# Multitouch_alaMTK.net
KiCad netlist of a schematic drawn in EasyEDA
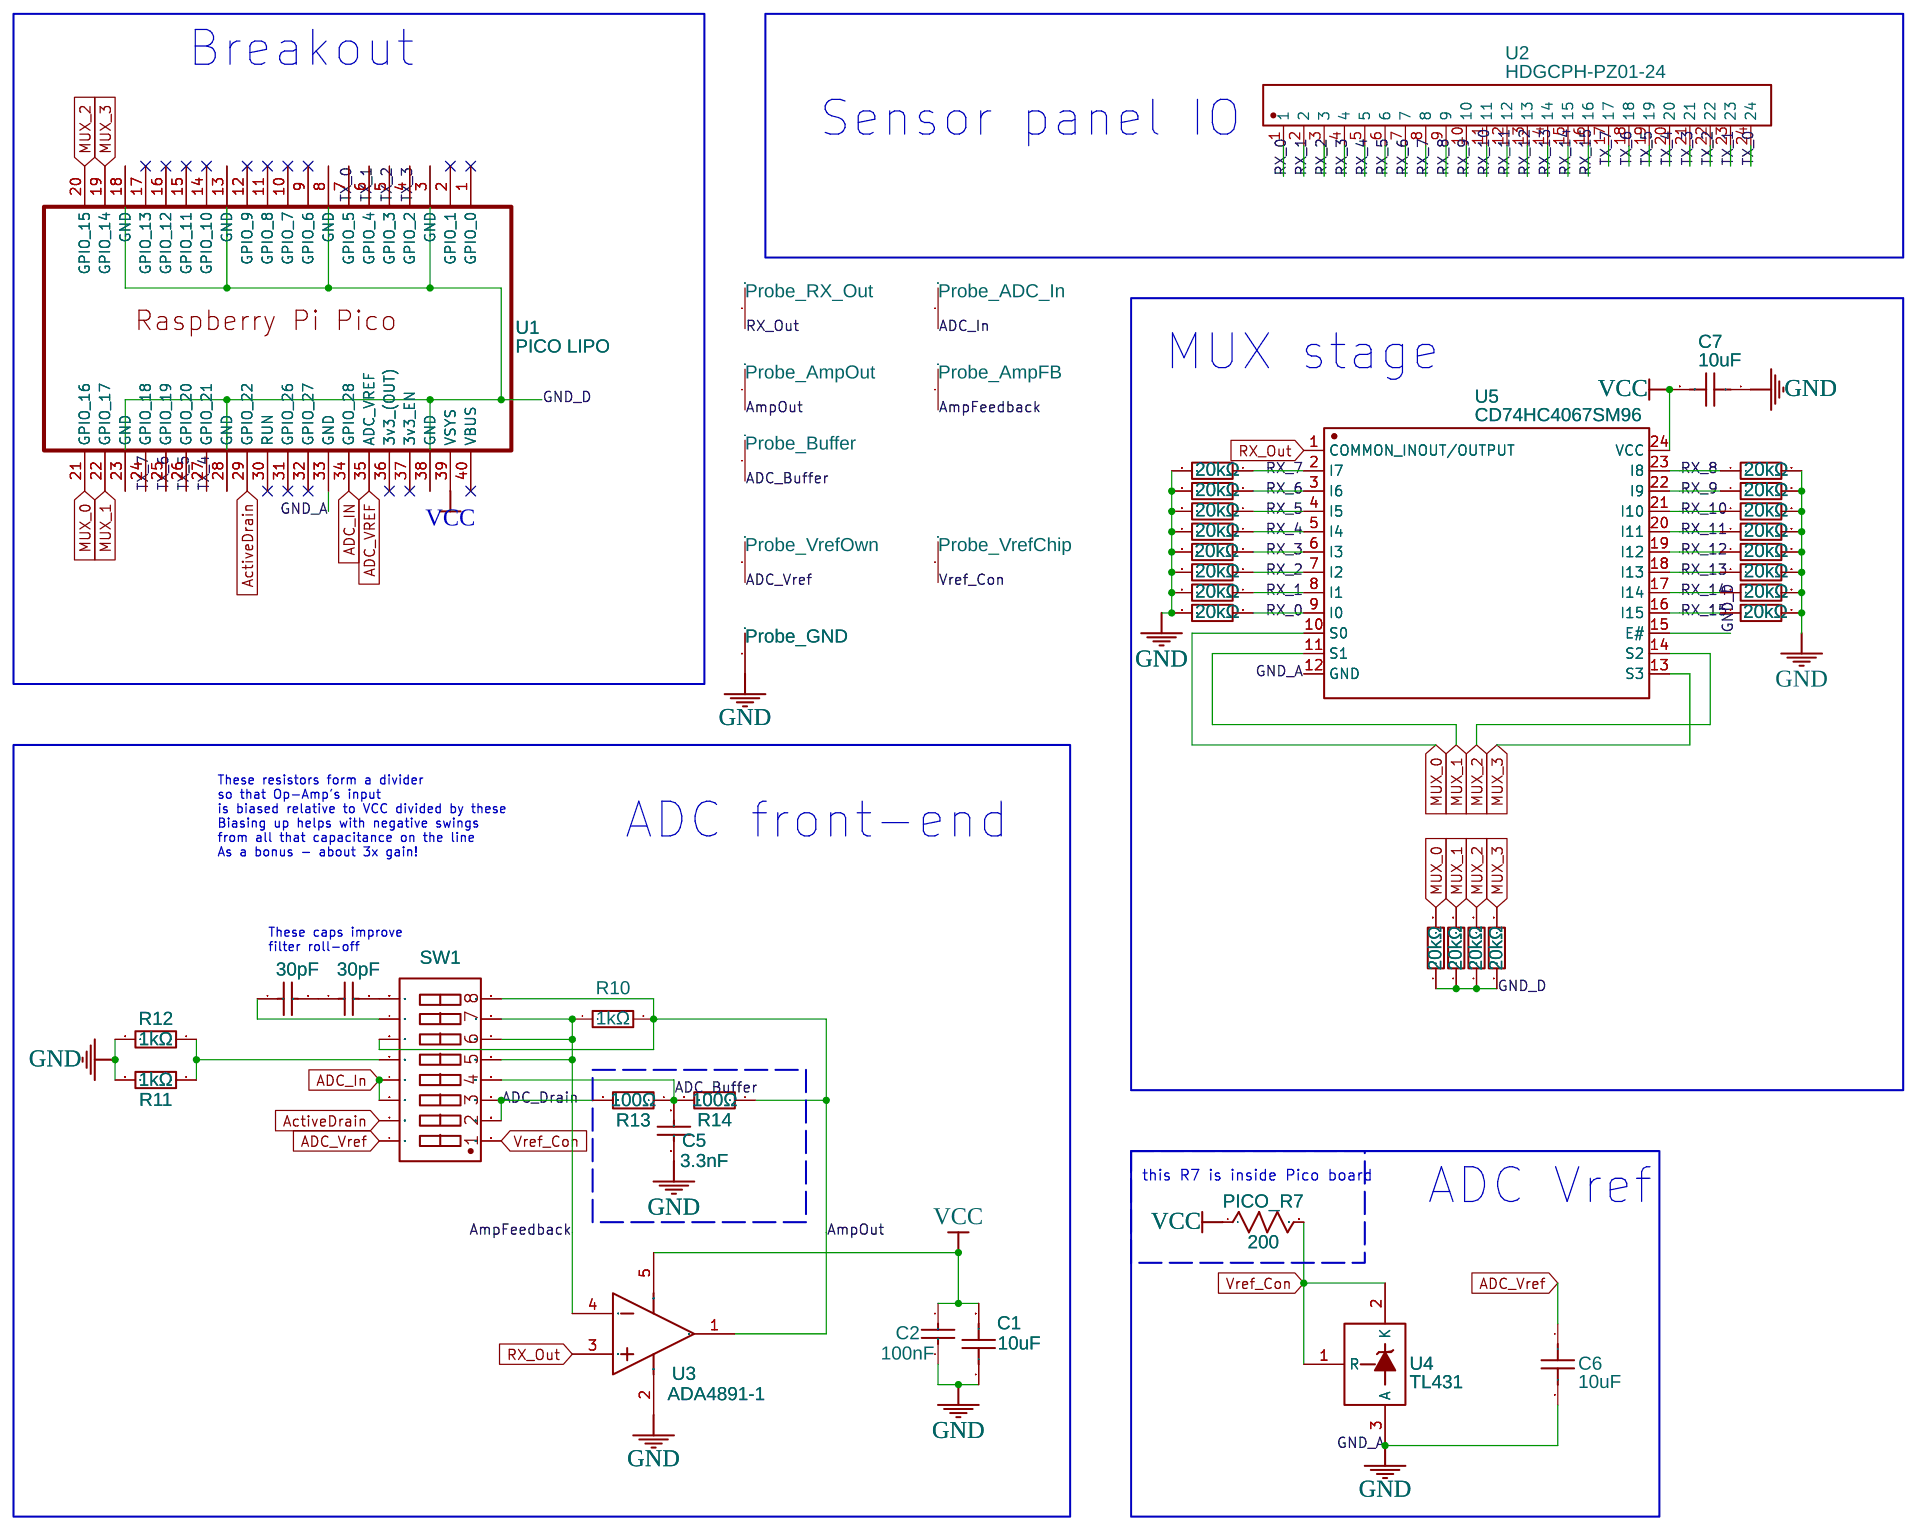
[diagram p0: schematic sheet]

(export (version "E")
  (design (tool "Eeschema 10.0.6"))
  (components
    (comp (ref "ADCB") (value "Probe_Buffer") (libsource (lib "") (part "SINGLE_PIN_1")))
    (comp (ref "ADCI") (value "Probe_ADC_In") (libsource (lib "") (part "SINGLE_PIN_7")))
    (comp (ref "ADCV") (value "Probe_VrefOwn") (libsource (lib "") (part "SINGLE_PIN_2")))
    (comp (ref "AFB") (value "Probe_AmpFB") (libsource (lib "") (part "SINGLE_PIN_3")))
    (comp (ref "AO") (value "Probe_AmpOut") (libsource (lib "") (part "SINGLE_PIN_5")))
    (comp (ref "C1")
      (value "10uF")
      (fields
        (field (name "Manufacturer Part") "CL10A106KP8NNNC")
        (field (name "Manufacturer") "SAMSUNG(三星)")
      )
      (libsource (lib "") (part "CL10A106KP8NNNC"))
    )
    (comp (ref "C2")
      (value "100nF")
      (fields
        (field (name "Manufacturer Part") "CL05B104KO5NNNC")
        (field (name "Manufacturer") "SAMSUNG(三星)")
      )
      (libsource (lib "") (part "CL05B104KO5NNNC"))
    )
    (comp (ref "C3")
      (value "30pF")
      (fields (field (name "Manufacturer Part") "0603CG300J500NT") (field (name "Manufacturer") "FH(风华)"))
      (libsource (lib "") (part "0603CG300J500NT"))
    )
    (comp (ref "C4")
      (value "30pF")
      (fields (field (name "Manufacturer Part") "0603CG300J500NT") (field (name "Manufacturer") "FH(风华)"))
      (libsource (lib "") (part "0603CG300J500NT"))
    )
    (comp (ref "C5")
      (value "3.3nF")
      (fields
        (field (name "Manufacturer Part") "CL10B332KB8NNNC")
        (field (name "Manufacturer") "SAMSUNG(三星)")
      )
      (libsource (lib "") (part "CL10B332KB8NNNC"))
    )
    (comp (ref "C6")
      (value "10uF")
      (fields
        (field (name "Manufacturer Part") "CL10A106KP8NNNC")
        (field (name "Manufacturer") "SAMSUNG(三星)")
      )
      (libsource (lib "") (part "CL10A106KP8NNNC_2"))
    )
    (comp (ref "C7")
      (value "10uF")
      (fields
        (field (name "Manufacturer Part") "CL10A106KP8NNNC")
        (field (name "Manufacturer") "SAMSUNG(三星)")
      )
      (libsource (lib "") (part "CL10A106KP8NNNC_1"))
    )
    (comp (ref "J2") (value "Probe_GND") (libsource (lib "") (part "SINGLE_PIN_4")))
    (comp (ref "PICO_R7") (value "200") (libsource (lib "") (part "R_0603_US")))
    (comp (ref "R10")
      (value "1kΩ")
      (fields
        (field (name "Manufacturer Part") "0402WGF1001TCE")
        (field (name "Manufacturer") "UNI-ROYAL(厚声)")
      )
      (libsource (lib "") (part "0402WGF1001TCE"))
    )
    (comp (ref "R11")
      (value "1kΩ")
      (fields
        (field (name "Manufacturer Part") "0402WGF1001TCE")
        (field (name "Manufacturer") "UNI-ROYAL(厚声)")
      )
      (libsource (lib "") (part "0402WGF1001TCE_1"))
    )
    (comp (ref "R12")
      (value "1kΩ")
      (fields
        (field (name "Manufacturer Part") "0402WGF1001TCE")
        (field (name "Manufacturer") "UNI-ROYAL(厚声)")
      )
      (libsource (lib "") (part "0402WGF1001TCE_1"))
    )
    (comp (ref "R13")
      (value "100Ω")
      (fields
        (field (name "Manufacturer Part") "0402WGF1000TCE")
        (field (name "Manufacturer") "UNI-ROYAL(厚声)")
      )
      (libsource (lib "") (part "0402WGF1000TCE"))
    )
    (comp (ref "R14")
      (value "100Ω")
      (fields
        (field (name "Manufacturer Part") "0402WGF1000TCE")
        (field (name "Manufacturer") "UNI-ROYAL(厚声)")
      )
      (libsource (lib "") (part "0402WGF1000TCE"))
    )
    (comp (ref "R15")
      (value "20kΩ")
      (fields
        (field (name "Manufacturer Part") "0402WGF2002TCE")
        (field (name "Manufacturer") "UNI-ROYAL(厚声)")
      )
      (libsource (lib "") (part "0402WGF2002TCE_1"))
    )
    (comp (ref "R16")
      (value "20kΩ")
      (fields
        (field (name "Manufacturer Part") "0402WGF2002TCE")
        (field (name "Manufacturer") "UNI-ROYAL(厚声)")
      )
      (libsource (lib "") (part "0402WGF2002TCE_1"))
    )
    (comp (ref "R17")
      (value "20kΩ")
      (fields
        (field (name "Manufacturer Part") "0402WGF2002TCE")
        (field (name "Manufacturer") "UNI-ROYAL(厚声)")
      )
      (libsource (lib "") (part "0402WGF2002TCE_1"))
    )
    (comp (ref "R18")
      (value "20kΩ")
      (fields
        (field (name "Manufacturer Part") "0402WGF2002TCE")
        (field (name "Manufacturer") "UNI-ROYAL(厚声)")
      )
      (libsource (lib "") (part "0402WGF2002TCE_1"))
    )
    (comp (ref "R19")
      (value "20kΩ")
      (fields
        (field (name "Manufacturer Part") "0402WGF2002TCE")
        (field (name "Manufacturer") "UNI-ROYAL(厚声)")
      )
      (libsource (lib "") (part "0402WGF2002TCE"))
    )
    (comp (ref "R20")
      (value "20kΩ")
      (fields
        (field (name "Manufacturer Part") "0402WGF2002TCE")
        (field (name "Manufacturer") "UNI-ROYAL(厚声)")
      )
      (libsource (lib "") (part "0402WGF2002TCE_2"))
    )
    (comp (ref "R21")
      (value "20kΩ")
      (fields
        (field (name "Manufacturer Part") "0402WGF2002TCE")
        (field (name "Manufacturer") "UNI-ROYAL(厚声)")
      )
      (libsource (lib "") (part "0402WGF2002TCE_2"))
    )
    (comp (ref "R22")
      (value "20kΩ")
      (fields
        (field (name "Manufacturer Part") "0402WGF2002TCE")
        (field (name "Manufacturer") "UNI-ROYAL(厚声)")
      )
      (libsource (lib "") (part "0402WGF2002TCE_2"))
    )
    (comp (ref "R23")
      (value "20kΩ")
      (fields
        (field (name "Manufacturer Part") "0402WGF2002TCE")
        (field (name "Manufacturer") "UNI-ROYAL(厚声)")
      )
      (libsource (lib "") (part "0402WGF2002TCE_2"))
    )
    (comp (ref "R24")
      (value "20kΩ")
      (fields
        (field (name "Manufacturer Part") "0402WGF2002TCE")
        (field (name "Manufacturer") "UNI-ROYAL(厚声)")
      )
      (libsource (lib "") (part "0402WGF2002TCE_2"))
    )
    (comp (ref "R25")
      (value "20kΩ")
      (fields
        (field (name "Manufacturer Part") "0402WGF2002TCE")
        (field (name "Manufacturer") "UNI-ROYAL(厚声)")
      )
      (libsource (lib "") (part "0402WGF2002TCE_2"))
    )
    (comp (ref "R26")
      (value "20kΩ")
      (fields
        (field (name "Manufacturer Part") "0402WGF2002TCE")
        (field (name "Manufacturer") "UNI-ROYAL(厚声)")
      )
      (libsource (lib "") (part "0402WGF2002TCE_2"))
    )
    (comp (ref "R27")
      (value "20kΩ")
      (fields
        (field (name "Manufacturer Part") "0402WGF2002TCE")
        (field (name "Manufacturer") "UNI-ROYAL(厚声)")
      )
      (libsource (lib "") (part "0402WGF2002TCE_2"))
    )
    (comp (ref "R28")
      (value "20kΩ")
      (fields
        (field (name "Manufacturer Part") "0402WGF2002TCE")
        (field (name "Manufacturer") "UNI-ROYAL(厚声)")
      )
      (libsource (lib "") (part "0402WGF2002TCE"))
    )
    (comp (ref "R29")
      (value "20kΩ")
      (fields
        (field (name "Manufacturer Part") "0402WGF2002TCE")
        (field (name "Manufacturer") "UNI-ROYAL(厚声)")
      )
      (libsource (lib "") (part "0402WGF2002TCE"))
    )
    (comp (ref "R30")
      (value "20kΩ")
      (fields
        (field (name "Manufacturer Part") "0402WGF2002TCE")
        (field (name "Manufacturer") "UNI-ROYAL(厚声)")
      )
      (libsource (lib "") (part "0402WGF2002TCE"))
    )
    (comp (ref "R31")
      (value "20kΩ")
      (fields
        (field (name "Manufacturer Part") "0402WGF2002TCE")
        (field (name "Manufacturer") "UNI-ROYAL(厚声)")
      )
      (libsource (lib "") (part "0402WGF2002TCE"))
    )
    (comp (ref "R32")
      (value "20kΩ")
      (fields
        (field (name "Manufacturer Part") "0402WGF2002TCE")
        (field (name "Manufacturer") "UNI-ROYAL(厚声)")
      )
      (libsource (lib "") (part "0402WGF2002TCE"))
    )
    (comp (ref "R33")
      (value "20kΩ")
      (fields
        (field (name "Manufacturer Part") "0402WGF2002TCE")
        (field (name "Manufacturer") "UNI-ROYAL(厚声)")
      )
      (libsource (lib "") (part "0402WGF2002TCE"))
    )
    (comp (ref "R34")
      (value "20kΩ")
      (fields
        (field (name "Manufacturer Part") "0402WGF2002TCE")
        (field (name "Manufacturer") "UNI-ROYAL(厚声)")
      )
      (libsource (lib "") (part "0402WGF2002TCE"))
    )
    (comp (ref "RXO") (value "Probe_RX_Out") (libsource (lib "") (part "SINGLE_PIN")))
    (comp (ref "SW1")
      (value "KF1027B-08P-L00-DFT-01B")
      (fields (field (name "Manufacturer") "凯峰"))
      (libsource (lib "") (part "KF1027B-08P-L00-DFT-01B"))
    )
    (comp (ref "U1") (value "PICO LIPO") (libsource (lib "") (part "RASPBERRY PI PICO WITH 3D MODEL COPY")))
    (comp (ref "U2")
      (value "HDGCPH-PZ01-24")
      (fields (field (name "Manufacturer") "HDGC(华德共创)"))
      (libsource (lib "") (part "HDGCPH-PZ01-24"))
    )
    (comp (ref "U3")
      (value "ADA4891-1")
      (fields (field (name "Manufacturer Part") "ADA4891-1ARJZ-R7") (field (name "Manufacturer") "ADI(亚德诺)"))
      (libsource (lib "") (part "ADA4891-1ARJZ-R7"))
    )
    (comp (ref "U4")
      (value "TL431")
      (fields (field (name "Manufacturer Part") "CJ431") (field (name "Manufacturer") "CJ(江苏长电/长晶)"))
      (libsource (lib "") (part "CJ431_C3113"))
    )
    (comp (ref "U5")
      (value "CD74HC4067SM96")
      (fields (field (name "Manufacturer") "TI(德州仪器)"))
      (libsource (lib "") (part "CD74HC4067SM96"))
    )
    (comp (ref "VREF") (value "Probe_VrefChip") (libsource (lib "") (part "SINGLE_PIN_6")))
  )
  (nets
    (net (code "1") (name "/ADC_Buffer") (class "Default")
      (node (ref "ADCB") (pin "1") (pinfunction "1_1") (pintype "unspecified"))
      (node (ref "C5") (pin "2") (pinfunction "2_2") (pintype "input"))
      (node (ref "R13") (pin "1") (pinfunction "1_1") (pintype "input"))
      (node (ref "R14") (pin "2") (pinfunction "2_2") (pintype "input"))
      (node (ref "SW1") (pin "12") (pinfunction "PIN12_12") (pintype "unspecified"))
    )
    (net (code "2") (name "/ADC_Drain") (class "Default")
      (node (ref "R13") (pin "2") (pinfunction "2_2") (pintype "input"))
      (node (ref "SW1") (pin "10") (pinfunction "PIN10_10") (pintype "unspecified"))
      (node (ref "SW1") (pin "11") (pinfunction "PIN11_11") (pintype "unspecified"))
    )
    (net (code "3") (name "/AmpFeedback") (class "Default")
      (node (ref "AFB") (pin "1") (pinfunction "1_1") (pintype "unspecified"))
      (node (ref "R10") (pin "1") (pinfunction "1_1") (pintype "input"))
      (node (ref "SW1") (pin "13") (pinfunction "PIN13_13") (pintype "unspecified"))
      (node (ref "SW1") (pin "14") (pinfunction "PIN14_14") (pintype "unspecified"))
      (node (ref "SW1") (pin "15") (pinfunction "15_15") (pintype "unspecified"))
      (node (ref "U3") (pin "4") (pinfunction "-IN_4") (pintype "unspecified"))
    )
    (net (code "4") (name "/AmpOut") (class "Default")
      (node (ref "AO") (pin "1") (pinfunction "1_1") (pintype "unspecified"))
      (node (ref "R10") (pin "2") (pinfunction "2_2") (pintype "input"))
      (node (ref "R14") (pin "1") (pinfunction "1_1") (pintype "input"))
      (node (ref "SW1") (pin "16") (pinfunction "16_16") (pintype "unspecified"))
      (node (ref "SW1") (pin "6") (pinfunction "PIN6_6") (pintype "unspecified"))
      (node (ref "U3") (pin "1") (pinfunction "OUT_1") (pintype "output"))
    )
    (net (code "5") (name "/GND_D") (class "Default")
      (node (ref "R15") (pin "1") (pinfunction "1_1") (pintype "input"))
      (node (ref "R16") (pin "1") (pinfunction "1_1") (pintype "input"))
      (node (ref "R17") (pin "1") (pinfunction "1_1") (pintype "input"))
      (node (ref "R18") (pin "1") (pinfunction "1_1") (pintype "input"))
      (node (ref "U1") (pin "13") (pinfunction "GND_13") (pintype "unspecified"))
      (node (ref "U1") (pin "18") (pinfunction "GND_18") (pintype "unspecified"))
      (node (ref "U1") (pin "23") (pinfunction "GND_23") (pintype "unspecified"))
      (node (ref "U1") (pin "28") (pinfunction "GND_28") (pintype "unspecified"))
      (node (ref "U1") (pin "3") (pinfunction "GND_3") (pintype "unspecified"))
      (node (ref "U1") (pin "38") (pinfunction "GND_38") (pintype "unspecified"))
      (node (ref "U1") (pin "8") (pinfunction "GND_8") (pintype "unspecified"))
      (node (ref "U5") (pin "15") (pinfunction "E#_15") (pintype "unspecified"))
    )
    (net (code "6") (name "/RX_0") (class "Default")
      (node (ref "R27") (pin "1") (pinfunction "1_1") (pintype "input"))
      (node (ref "U2") (pin "1") (pinfunction "1_1") (pintype "unspecified"))
      (node (ref "U5") (pin "9") (pinfunction "I0_9") (pintype "unspecified"))
    )
    (net (code "7") (name "/RX_1") (class "Default")
      (node (ref "R26") (pin "1") (pinfunction "1_1") (pintype "input"))
      (node (ref "U2") (pin "2") (pinfunction "2_2") (pintype "unspecified"))
      (node (ref "U5") (pin "8") (pinfunction "I1_8") (pintype "unspecified"))
    )
    (net (code "8") (name "/RX_2") (class "Default")
      (node (ref "R25") (pin "1") (pinfunction "1_1") (pintype "input"))
      (node (ref "U2") (pin "3") (pinfunction "3_3") (pintype "unspecified"))
      (node (ref "U5") (pin "7") (pinfunction "I2_7") (pintype "unspecified"))
    )
    (net (code "9") (name "/RX_3") (class "Default")
      (node (ref "R24") (pin "1") (pinfunction "1_1") (pintype "input"))
      (node (ref "U2") (pin "4") (pinfunction "4_4") (pintype "unspecified"))
      (node (ref "U5") (pin "6") (pinfunction "I3_6") (pintype "unspecified"))
    )
    (net (code "10") (name "/RX_4") (class "Default")
      (node (ref "R23") (pin "1") (pinfunction "1_1") (pintype "input"))
      (node (ref "U2") (pin "5") (pinfunction "5_5") (pintype "unspecified"))
      (node (ref "U5") (pin "5") (pinfunction "I4_5") (pintype "unspecified"))
    )
    (net (code "11") (name "/RX_5") (class "Default")
      (node (ref "R22") (pin "1") (pinfunction "1_1") (pintype "input"))
      (node (ref "U2") (pin "6") (pinfunction "6_6") (pintype "unspecified"))
      (node (ref "U5") (pin "4") (pinfunction "I5_4") (pintype "unspecified"))
    )
    (net (code "12") (name "/RX_6") (class "Default")
      (node (ref "R21") (pin "1") (pinfunction "1_1") (pintype "input"))
      (node (ref "U2") (pin "7") (pinfunction "7_7") (pintype "unspecified"))
      (node (ref "U5") (pin "3") (pinfunction "I6_3") (pintype "unspecified"))
    )
    (net (code "13") (name "/RX_7") (class "Default")
      (node (ref "R20") (pin "1") (pinfunction "1_1") (pintype "input"))
      (node (ref "U2") (pin "8") (pinfunction "8_8") (pintype "unspecified"))
      (node (ref "U5") (pin "2") (pinfunction "I7_2") (pintype "unspecified"))
    )
    (net (code "14") (name "/RX_8") (class "Default")
      (node (ref "R19") (pin "1") (pinfunction "1_1") (pintype "input"))
      (node (ref "U2") (pin "9") (pinfunction "9_9") (pintype "unspecified"))
      (node (ref "U5") (pin "23") (pinfunction "I8_23") (pintype "unspecified"))
    )
    (net (code "15") (name "/RX_9") (class "Default")
      (node (ref "R28") (pin "1") (pinfunction "1_1") (pintype "input"))
      (node (ref "U2") (pin "10") (pinfunction "10_10") (pintype "unspecified"))
      (node (ref "U5") (pin "22") (pinfunction "I9_22") (pintype "unspecified"))
    )
    (net (code "16") (name "/RX_10") (class "Default")
      (node (ref "R29") (pin "1") (pinfunction "1_1") (pintype "input"))
      (node (ref "U2") (pin "11") (pinfunction "11_11") (pintype "unspecified"))
      (node (ref "U5") (pin "21") (pinfunction "I10_21") (pintype "unspecified"))
    )
    (net (code "17") (name "/RX_11") (class "Default")
      (node (ref "R30") (pin "1") (pinfunction "1_1") (pintype "input"))
      (node (ref "U2") (pin "12") (pinfunction "12_12") (pintype "unspecified"))
      (node (ref "U5") (pin "20") (pinfunction "I11_20") (pintype "unspecified"))
    )
    (net (code "18") (name "/RX_12") (class "Default")
      (node (ref "R31") (pin "1") (pinfunction "1_1") (pintype "input"))
      (node (ref "U2") (pin "13") (pinfunction "13_13") (pintype "unspecified"))
      (node (ref "U5") (pin "19") (pinfunction "I12_19") (pintype "unspecified"))
    )
    (net (code "19") (name "/RX_13") (class "Default")
      (node (ref "R32") (pin "1") (pinfunction "1_1") (pintype "input"))
      (node (ref "U2") (pin "14") (pinfunction "14_14") (pintype "unspecified"))
      (node (ref "U5") (pin "18") (pinfunction "I13_18") (pintype "unspecified"))
    )
    (net (code "20") (name "/RX_14") (class "Default")
      (node (ref "R33") (pin "1") (pinfunction "1_1") (pintype "input"))
      (node (ref "U2") (pin "15") (pinfunction "15_15") (pintype "unspecified"))
      (node (ref "U5") (pin "17") (pinfunction "I14_17") (pintype "unspecified"))
    )
    (net (code "21") (name "/RX_15") (class "Default")
      (node (ref "R34") (pin "1") (pinfunction "1_1") (pintype "input"))
      (node (ref "U2") (pin "16") (pinfunction "16_16") (pintype "unspecified"))
      (node (ref "U5") (pin "16") (pinfunction "I15_16") (pintype "unspecified"))
    )
    (net (code "22") (name "/TX_0") (class "Default")
      (node (ref "U1") (pin "7") (pinfunction "GPIO_5_7") (pintype "unspecified"))
      (node (ref "U2") (pin "24") (pinfunction "24_24") (pintype "unspecified"))
    )
    (net (code "23") (name "/TX_1") (class "Default")
      (node (ref "U1") (pin "6") (pinfunction "GPIO_4_6") (pintype "unspecified"))
      (node (ref "U2") (pin "23") (pinfunction "23_23") (pintype "unspecified"))
    )
    (net (code "24") (name "/TX_2") (class "Default")
      (node (ref "U1") (pin "5") (pinfunction "GPIO_3_5") (pintype "unspecified"))
      (node (ref "U2") (pin "22") (pinfunction "22_22") (pintype "unspecified"))
    )
    (net (code "25") (name "/TX_3") (class "Default")
      (node (ref "U1") (pin "4") (pinfunction "GPIO_2_4") (pintype "unspecified"))
      (node (ref "U2") (pin "21") (pinfunction "21_21") (pintype "unspecified"))
    )
    (net (code "26") (name "/TX_4") (class "Default")
      (node (ref "U1") (pin "27") (pinfunction "GPIO_21_27") (pintype "unspecified"))
      (node (ref "U2") (pin "20") (pinfunction "20_20") (pintype "unspecified"))
    )
    (net (code "27") (name "/TX_5") (class "Default")
      (node (ref "U1") (pin "26") (pinfunction "GPIO_20_26") (pintype "unspecified"))
      (node (ref "U2") (pin "19") (pinfunction "19_19") (pintype "unspecified"))
    )
    (net (code "28") (name "/TX_6") (class "Default")
      (node (ref "U1") (pin "25") (pinfunction "GPIO_19_25") (pintype "unspecified"))
      (node (ref "U2") (pin "18") (pinfunction "18_18") (pintype "unspecified"))
    )
    (net (code "29") (name "/TX_7") (class "Default")
      (node (ref "U1") (pin "24") (pinfunction "GPIO_18_24") (pintype "unspecified"))
      (node (ref "U2") (pin "17") (pinfunction "17_17") (pintype "unspecified"))
    )
    (net (code "30") (name "ADC_IN") (class "Default")
      (node (ref "U1") (pin "34") (pinfunction "GPIO_28_34") (pintype "unspecified"))
    )
    (net (code "31") (name "ADC_In") (class "Default")
      (node (ref "ADCI") (pin "1") (pinfunction "1_1") (pintype "unspecified"))
      (node (ref "SW1") (pin "3") (pinfunction "PIN3_3") (pintype "unspecified"))
      (node (ref "SW1") (pin "4") (pinfunction "PIN4_4") (pintype "unspecified"))
    )
    (net (code "32") (name "ADC_VREF") (class "Default")
      (node (ref "U1") (pin "35") (pinfunction "ADC_VREF_35") (pintype "unspecified"))
    )
    (net (code "33") (name "ADC_Vref") (class "Default")
      (node (ref "ADCV") (pin "1") (pinfunction "1_1") (pintype "unspecified"))
      (node (ref "C6") (pin "1") (pinfunction "1_1") (pintype "unspecified"))
      (node (ref "SW1") (pin "1") (pinfunction "PIN1_1") (pintype "unspecified"))
    )
    (net (code "34") (name "ActiveDrain") (class "Default")
      (node (ref "SW1") (pin "2") (pinfunction "PIN2_2") (pintype "unspecified"))
      (node (ref "U1") (pin "29") (pinfunction "GPIO_22_29") (pintype "unspecified"))
    )
    (net (code "35") (name "GND") (class "Default")
      (node (ref "C1") (pin "1") (pinfunction "1_1") (pintype "unspecified"))
      (node (ref "C2") (pin "1") (pinfunction "1_1") (pintype "input"))
      (node (ref "C5") (pin "1") (pinfunction "1_1") (pintype "input"))
      (node (ref "C6") (pin "2") (pinfunction "2_2") (pintype "unspecified"))
      (node (ref "C7") (pin "1") (pinfunction "1_1") (pintype "unspecified"))
      (node (ref "J2") (pin "1") (pinfunction "1_1") (pintype "unspecified"))
      (node (ref "R11") (pin "2") (pinfunction "2_2") (pintype "input"))
      (node (ref "R12") (pin "2") (pinfunction "2_2") (pintype "input"))
      (node (ref "R19") (pin "2") (pinfunction "2_2") (pintype "input"))
      (node (ref "R20") (pin "2") (pinfunction "2_2") (pintype "input"))
      (node (ref "R21") (pin "2") (pinfunction "2_2") (pintype "input"))
      (node (ref "R22") (pin "2") (pinfunction "2_2") (pintype "input"))
      (node (ref "R23") (pin "2") (pinfunction "2_2") (pintype "input"))
      (node (ref "R24") (pin "2") (pinfunction "2_2") (pintype "input"))
      (node (ref "R25") (pin "2") (pinfunction "2_2") (pintype "input"))
      (node (ref "R26") (pin "2") (pinfunction "2_2") (pintype "input"))
      (node (ref "R27") (pin "2") (pinfunction "2_2") (pintype "input"))
      (node (ref "R28") (pin "2") (pinfunction "2_2") (pintype "input"))
      (node (ref "R29") (pin "2") (pinfunction "2_2") (pintype "input"))
      (node (ref "R30") (pin "2") (pinfunction "2_2") (pintype "input"))
      (node (ref "R31") (pin "2") (pinfunction "2_2") (pintype "input"))
      (node (ref "R32") (pin "2") (pinfunction "2_2") (pintype "input"))
      (node (ref "R33") (pin "2") (pinfunction "2_2") (pintype "input"))
      (node (ref "R34") (pin "2") (pinfunction "2_2") (pintype "input"))
      (node (ref "U1") (pin "33") (pinfunction "GND_33") (pintype "unspecified"))
      (node (ref "U3") (pin "2") (pinfunction "-VS_2") (pintype "passive"))
      (node (ref "U4") (pin "3") (pinfunction "A_3") (pintype "unspecified"))
      (node (ref "U5") (pin "12") (pinfunction "GND_12") (pintype "unspecified"))
    )
    (net (code "36") (name "MUX_0") (class "Default")
      (node (ref "R18") (pin "2") (pinfunction "2_2") (pintype "input"))
      (node (ref "U1") (pin "21") (pinfunction "GPIO_16_21") (pintype "unspecified"))
      (node (ref "U5") (pin "10") (pinfunction "S0_10") (pintype "unspecified"))
    )
    (net (code "37") (name "MUX_1") (class "Default")
      (node (ref "R17") (pin "2") (pinfunction "2_2") (pintype "input"))
      (node (ref "U1") (pin "22") (pinfunction "GPIO_17_22") (pintype "unspecified"))
      (node (ref "U5") (pin "11") (pinfunction "S1_11") (pintype "unspecified"))
    )
    (net (code "38") (name "MUX_2") (class "Default")
      (node (ref "R16") (pin "2") (pinfunction "2_2") (pintype "input"))
      (node (ref "U1") (pin "20") (pinfunction "GPIO_15_20") (pintype "unspecified"))
      (node (ref "U5") (pin "14") (pinfunction "S2_14") (pintype "unspecified"))
    )
    (net (code "39") (name "MUX_3") (class "Default")
      (node (ref "R15") (pin "2") (pinfunction "2_2") (pintype "input"))
      (node (ref "U1") (pin "19") (pinfunction "GPIO_14_19") (pintype "unspecified"))
      (node (ref "U5") (pin "13") (pinfunction "S3_13") (pintype "unspecified"))
    )
    (net (code "40") (name "Net-(C3-Pad1)") (class "Default")
      (node (ref "C3") (pin "1") (pinfunction "1_1") (pintype "input"))
      (node (ref "C4") (pin "2") (pinfunction "2_2") (pintype "input"))
    )
    (net (code "41") (name "Net-(SW1-PIN5)") (class "Default")
      (node (ref "R11") (pin "1") (pinfunction "1_1") (pintype "input"))
      (node (ref "R12") (pin "1") (pinfunction "1_1") (pintype "input"))
      (node (ref "SW1") (pin "5") (pinfunction "PIN5_5") (pintype "unspecified"))
    )
    (net (code "42") (name "Net-(SW1-PIN7)") (class "Default")
      (node (ref "C4") (pin "1") (pinfunction "1_1") (pintype "input"))
      (node (ref "SW1") (pin "7") (pinfunction "PIN7_7") (pintype "unspecified"))
    )
    (net (code "43") (name "Net-(SW1-PIN8)") (class "Default")
      (node (ref "C3") (pin "2") (pinfunction "2_2") (pintype "input"))
      (node (ref "SW1") (pin "8") (pinfunction "PIN8_8") (pintype "unspecified"))
    )
    (net (code "44") (name "RX_Out") (class "Default")
      (node (ref "RXO") (pin "1") (pinfunction "1_1") (pintype "unspecified"))
      (node (ref "U3") (pin "3") (pinfunction "+IN_3") (pintype "unspecified"))
      (node (ref "U5") (pin "1") (pinfunction "COMMON_INOUT/OUTPUT_1") (pintype "unspecified"))
    )
    (net (code "45") (name "VCC") (class "Default")
      (node (ref "C1") (pin "2") (pinfunction "2_2") (pintype "unspecified"))
      (node (ref "C2") (pin "2") (pinfunction "2_2") (pintype "input"))
      (node (ref "C7") (pin "2") (pinfunction "2_2") (pintype "unspecified"))
      (node (ref "PICO_R7") (pin "1") (pinfunction "1_1") (pintype "unspecified"))
      (node (ref "U1") (pin "39") (pinfunction "VSYS_39") (pintype "unspecified"))
      (node (ref "U3") (pin "5") (pinfunction "+VS_5") (pintype "passive"))
      (node (ref "U5") (pin "24") (pinfunction "VCC_24") (pintype "unspecified"))
    )
    (net (code "46") (name "Vref_Con") (class "Default")
      (node (ref "PICO_R7") (pin "2") (pinfunction "2_2") (pintype "unspecified"))
      (node (ref "SW1") (pin "9") (pinfunction "PIN9_9") (pintype "unspecified"))
      (node (ref "U4") (pin "1") (pinfunction "R_1") (pintype "unspecified"))
      (node (ref "U4") (pin "2") (pinfunction "K_2") (pintype "unspecified"))
      (node (ref "VREF") (pin "1") (pinfunction "1_1") (pintype "unspecified"))
    )
    (net (code "47") (name "unconnected-(U1-3v3_(OUT)-Pad36)") (class "Default")
      (node (ref "U1") (pin "36") (pinfunction "3v3_(OUT)_36") (pintype "unspecified+no_connect"))
    )
    (net (code "48") (name "unconnected-(U1-3v3_EN-Pad37)") (class "Default")
      (node (ref "U1") (pin "37") (pinfunction "3v3_EN_37") (pintype "unspecified+no_connect"))
    )
    (net (code "49") (name "unconnected-(U1-GPIO_0-Pad1)") (class "Default")
      (node (ref "U1") (pin "1") (pinfunction "GPIO_0_1") (pintype "unspecified+no_connect"))
    )
    (net (code "50") (name "unconnected-(U1-GPIO_1-Pad2)") (class "Default")
      (node (ref "U1") (pin "2") (pinfunction "GPIO_1_2") (pintype "unspecified+no_connect"))
    )
    (net (code "51") (name "unconnected-(U1-GPIO_6-Pad9)") (class "Default")
      (node (ref "U1") (pin "9") (pinfunction "GPIO_6_9") (pintype "unspecified+no_connect"))
    )
    (net (code "52") (name "unconnected-(U1-GPIO_7-Pad10)") (class "Default")
      (node (ref "U1") (pin "10") (pinfunction "GPIO_7_10") (pintype "unspecified+no_connect"))
    )
    (net (code "53") (name "unconnected-(U1-GPIO_8-Pad11)") (class "Default")
      (node (ref "U1") (pin "11") (pinfunction "GPIO_8_11") (pintype "unspecified+no_connect"))
    )
    (net (code "54") (name "unconnected-(U1-GPIO_9-Pad12)") (class "Default")
      (node (ref "U1") (pin "12") (pinfunction "GPIO_9_12") (pintype "unspecified+no_connect"))
    )
    (net (code "55") (name "unconnected-(U1-GPIO_10-Pad14)") (class "Default")
      (node (ref "U1") (pin "14") (pinfunction "GPIO_10_14") (pintype "unspecified+no_connect"))
    )
    (net (code "56") (name "unconnected-(U1-GPIO_11-Pad15)") (class "Default")
      (node (ref "U1") (pin "15") (pinfunction "GPIO_11_15") (pintype "unspecified+no_connect"))
    )
    (net (code "57") (name "unconnected-(U1-GPIO_12-Pad16)") (class "Default")
      (node (ref "U1") (pin "16") (pinfunction "GPIO_12_16") (pintype "unspecified+no_connect"))
    )
    (net (code "58") (name "unconnected-(U1-GPIO_13-Pad17)") (class "Default")
      (node (ref "U1") (pin "17") (pinfunction "GPIO_13_17") (pintype "unspecified+no_connect"))
    )
    (net (code "59") (name "unconnected-(U1-GPIO_26-Pad31)") (class "Default")
      (node (ref "U1") (pin "31") (pinfunction "GPIO_26_31") (pintype "unspecified+no_connect"))
    )
    (net (code "60") (name "unconnected-(U1-GPIO_27-Pad32)") (class "Default")
      (node (ref "U1") (pin "32") (pinfunction "GPIO_27_32") (pintype "unspecified+no_connect"))
    )
    (net (code "61") (name "unconnected-(U1-RUN-Pad30)") (class "Default")
      (node (ref "U1") (pin "30") (pinfunction "RUN_30") (pintype "unspecified+no_connect"))
    )
    (net (code "62") (name "unconnected-(U1-VBUS-Pad40)") (class "Default")
      (node (ref "U1") (pin "40") (pinfunction "VBUS_40") (pintype "unspecified+no_connect"))
    )
  )
)
